# LightSensorSchematic.net
KiCad netlist of a schematic drawn in Altium Designer
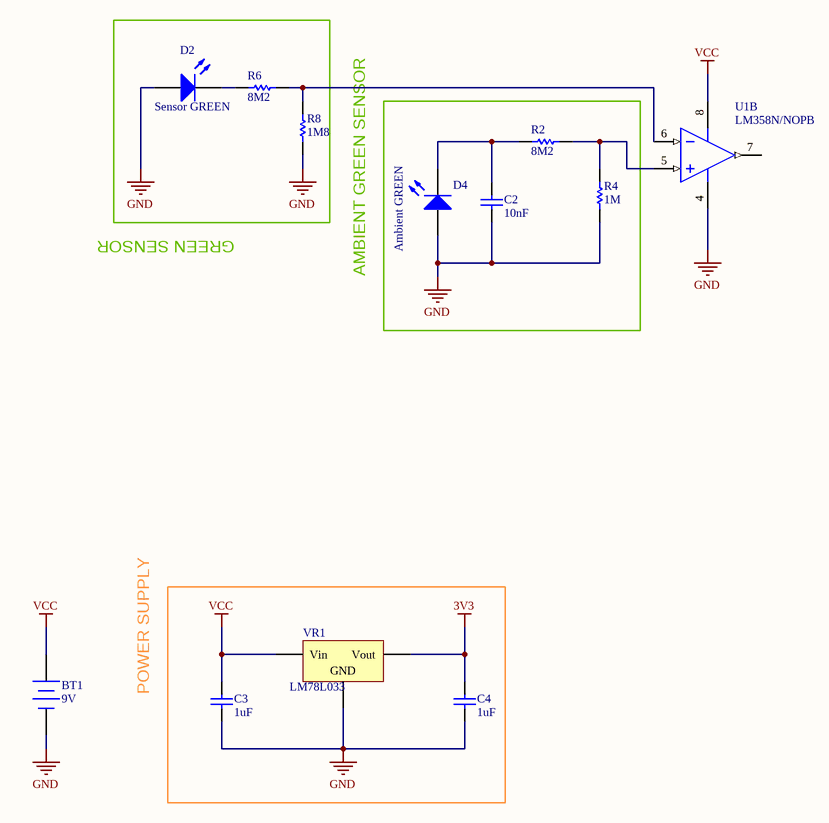
[diagram p0: LightSensorSchematic.SchDoc]

(export (version "E")
  (design (tool "Eeschema 10.0.6"))
  (components
    (comp (ref "BT1")
      (value "9V")
      (footprint "BAT-2")
      (description "Multicell Battery")
      (fields (field (name "PUBLISHER") "Altium Limited"))
      (libsource (lib "Miscellaneous Devices") (part "Battery"))
    )
    (comp (ref "C2")
      (value "10nF")
      (footprint "RAD-0.3")
      (description "Capacitor")
      (fields (field (name "PUBLISHER") "Altium Limited"))
      (libsource (lib "Miscellaneous Devices") (part "Cap"))
    )
    (comp (ref "C3")
      (value "1uF")
      (footprint "RAD-0.3")
      (description "Capacitor")
      (fields (field (name "PUBLISHER") "Altium Limited"))
      (libsource (lib "Miscellaneous Devices") (part "Cap"))
    )
    (comp (ref "C4")
      (value "1uF")
      (footprint "RAD-0.3")
      (description "Capacitor")
      (fields (field (name "PUBLISHER") "Altium Limited"))
      (libsource (lib "Miscellaneous Devices") (part "Cap"))
    )
    (comp (ref "D2")
      (value "Sensor GREEN")
      (footprint "LED-0")
      (description "Typical INFRARED GaAs LED")
      (fields (field (name "PUBLISHER") "Altium Limited"))
      (libsource (lib "Miscellaneous Devices") (part "LED0"))
    )
    (comp (ref "D4")
      (value "Ambient GREEN")
      (footprint "LED-0")
      (description "Typical INFRARED GaAs LED")
      (fields (field (name "PUBLISHER") "Altium Limited"))
      (libsource (lib "Miscellaneous Devices") (part "LED0"))
    )
    (comp (ref "R2")
      (value "8M2")
      (footprint "AXIAL-0.3")
      (description "Resistor")
      (fields (field (name "PUBLISHER") "Altium Limited"))
      (libsource (lib "Miscellaneous Devices") (part "Res1"))
    )
    (comp (ref "R4")
      (value "1M")
      (footprint "AXIAL-0.3")
      (description "Resistor")
      (fields (field (name "PUBLISHER") "Altium Limited"))
      (libsource (lib "Miscellaneous Devices") (part "Res1"))
    )
    (comp (ref "R6")
      (value "8M2")
      (footprint "AXIAL-0.3")
      (description "Resistor")
      (fields (field (name "PUBLISHER") "Altium Limited"))
      (libsource (lib "Miscellaneous Devices") (part "Res1"))
    )
    (comp (ref "R8")
      (value "1M8")
      (footprint "AXIAL-0.3")
      (description "Resistor")
      (fields (field (name "PUBLISHER") "Altium Limited"))
      (libsource (lib "Miscellaneous Devices") (part "Res1"))
    )
    (comp (ref "U1")
      (value "LM358N/NOPB")
      (footprint "N08E")
      (description "Low Power Dual Operational Amplifier, 8-pin MDIP, Pb-Free")
      (fields (field (name "MANUFACTURER") "National Semiconductor"))
      (libsource (lib "Altium Content Vault") (part "AMP-OPA-LM158-8"))
    )
    (comp (ref "VR1")
      (value "LM78L033")
      (footprint "D2PAK_N")
      (description "Voltage Regulator")
      (fields (field (name "PUBLISHER") "Altium Limited"))
      (libsource (lib "Miscellaneous Devices") (part "Volt Reg"))
    )
  )
  (nets
    (net (code "1") (name "3V3") (class "Default")
      (node (ref "C4") (pin "2") (pinfunction "2_2") (pintype "passive"))
      (node (ref "VR1") (pin "3") (pinfunction "Vout_3") (pintype "passive"))
    )
    (net (code "2") (name "GND") (class "Default")
      (node (ref "BT1") (pin "2") (pinfunction "-_2") (pintype "passive"))
      (node (ref "C2") (pin "1") (pinfunction "1_1") (pintype "passive"))
      (node (ref "C3") (pin "1") (pinfunction "1_1") (pintype "passive"))
      (node (ref "C4") (pin "1") (pinfunction "1_1") (pintype "passive"))
      (node (ref "D2") (pin "1") (pinfunction "A_1") (pintype "passive"))
      (node (ref "D4") (pin "1") (pinfunction "A_1") (pintype "passive"))
      (node (ref "R4") (pin "1") (pinfunction "1_1") (pintype "passive"))
      (node (ref "R8") (pin "1") (pinfunction "1_1") (pintype "passive"))
      (node (ref "U1") (pin "4") (pinfunction "GND_4") (pintype "power_in"))
      (node (ref "VR1") (pin "2") (pinfunction "GND_2") (pintype "passive"))
    )
    (net (code "3") (name "Net-(D2-K)") (class "Default")
      (node (ref "D2") (pin "2") (pinfunction "K_2") (pintype "passive"))
      (node (ref "R6") (pin "1") (pinfunction "1_1") (pintype "passive"))
    )
    (net (code "4") (name "Net-(D4-K)") (class "Default")
      (node (ref "C2") (pin "2") (pinfunction "2_2") (pintype "passive"))
      (node (ref "D4") (pin "2") (pinfunction "K_2") (pintype "passive"))
      (node (ref "R2") (pin "1") (pinfunction "1_1") (pintype "passive"))
    )
    (net (code "5") (name "Net-(U1B-INB+)") (class "Default")
      (node (ref "R2") (pin "2") (pinfunction "2_2") (pintype "passive"))
      (node (ref "R4") (pin "2") (pinfunction "2_2") (pintype "passive"))
      (node (ref "U1") (pin "5") (pinfunction "INB+_5") (pintype "input"))
    )
    (net (code "6") (name "Net-(U1B-INB-)") (class "Default")
      (node (ref "R6") (pin "2") (pinfunction "2_2") (pintype "passive"))
      (node (ref "R8") (pin "2") (pinfunction "2_2") (pintype "passive"))
      (node (ref "U1") (pin "6") (pinfunction "INB-_6") (pintype "input"))
    )
    (net (code "7") (name "VCC") (class "Default")
      (node (ref "BT1") (pin "1") (pinfunction "+_1") (pintype "passive"))
      (node (ref "C3") (pin "2") (pinfunction "2_2") (pintype "passive"))
      (node (ref "U1") (pin "8") (pinfunction "V+_8") (pintype "power_in"))
      (node (ref "VR1") (pin "1") (pinfunction "Vin_1") (pintype "passive"))
    )
    (net (code "8") (name "unconnected-(U1B-OUTB-Pad7)") (class "Default")
      (node (ref "U1") (pin "7") (pinfunction "OUTB_7") (pintype "output"))
    )
  )
)
